# ADC_Keychain.net
KiCad netlist of a schematic drawn in EAGLE
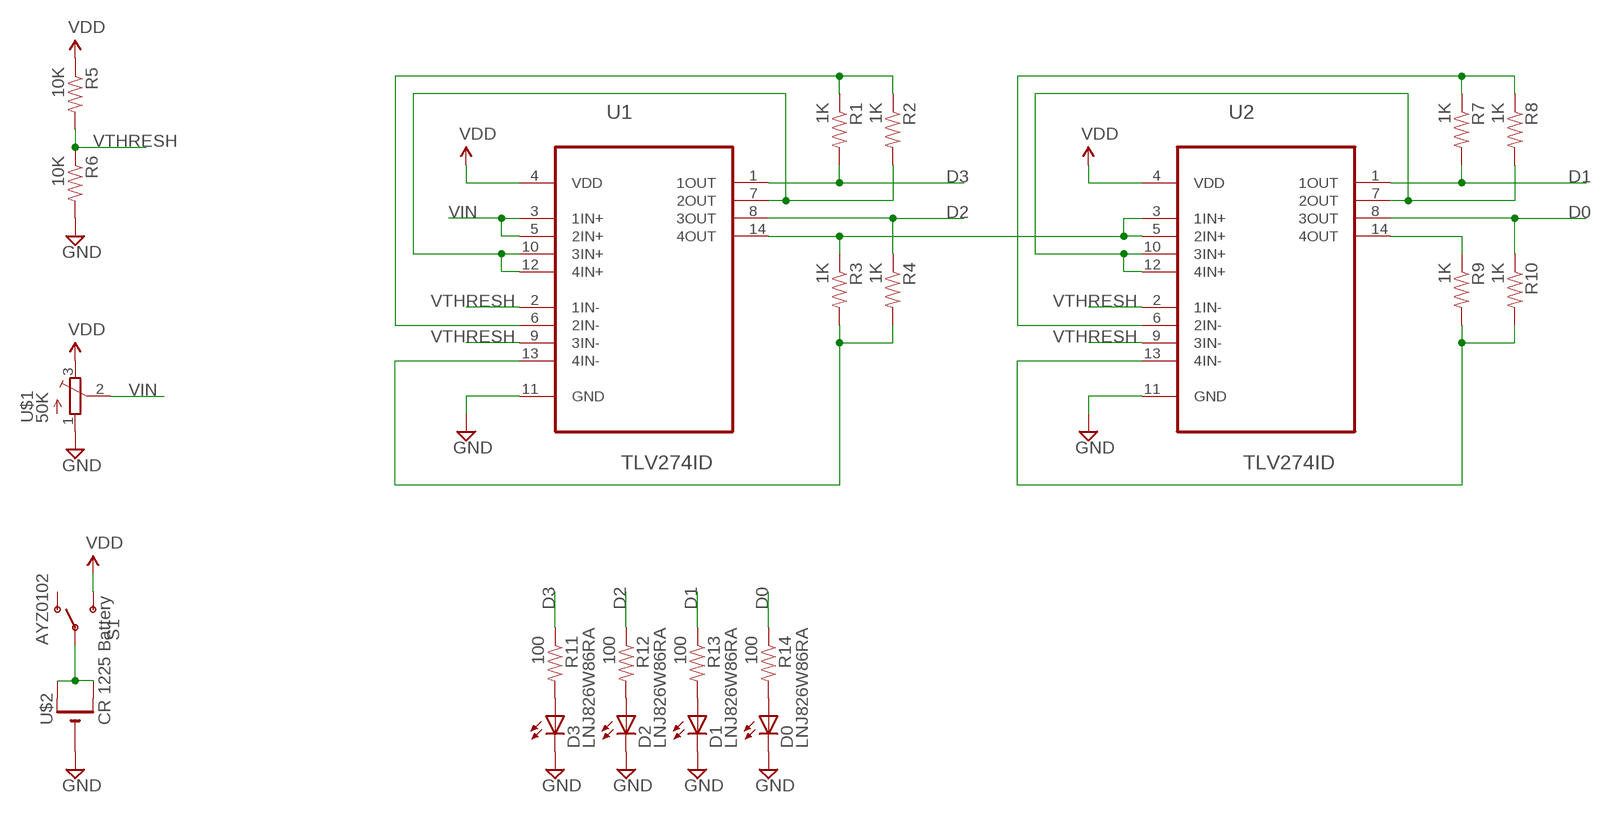
[diagram p0: schematic, sheet 1]

(export (version "E")
  (design (tool "Eeschema 10.0.6"))
  (components
    (comp (ref "D0")
      (value "LNJ826W86RA")
      (footprint "eagle-import:CHIP-LED0603")
      (libsource (lib "eagle-import") (part "LEDCHIP-LED0603"))
    )
    (comp (ref "D1")
      (value "LNJ826W86RA")
      (footprint "eagle-import:CHIP-LED0603")
      (libsource (lib "eagle-import") (part "LEDCHIP-LED0603"))
    )
    (comp (ref "D2")
      (value "LNJ826W86RA")
      (footprint "eagle-import:CHIP-LED0603")
      (libsource (lib "eagle-import") (part "LEDCHIP-LED0603"))
    )
    (comp (ref "D3")
      (value "LNJ826W86RA")
      (footprint "eagle-import:CHIP-LED0603")
      (libsource (lib "eagle-import") (part "LEDCHIP-LED0603"))
    )
    (comp (ref "R1")
      (value "1K")
      (footprint "eagle-import:0603-RES")
      (libsource (lib "eagle-import") (part "1KOHM1/10W1%(0603)"))
    )
    (comp (ref "R2")
      (value "1K")
      (footprint "eagle-import:0603-RES")
      (libsource (lib "eagle-import") (part "1KOHM1/10W1%(0603)"))
    )
    (comp (ref "R3")
      (value "1K")
      (footprint "eagle-import:0603-RES")
      (libsource (lib "eagle-import") (part "1KOHM1/10W1%(0603)"))
    )
    (comp (ref "R4")
      (value "1K")
      (footprint "eagle-import:0603-RES")
      (libsource (lib "eagle-import") (part "1KOHM1/10W1%(0603)"))
    )
    (comp (ref "R5")
      (value "10K")
      (footprint "eagle-import:0603-RES")
      (libsource (lib "eagle-import") (part "1KOHM1/10W1%(0603)"))
    )
    (comp (ref "R6")
      (value "10K")
      (footprint "eagle-import:0603-RES")
      (libsource (lib "eagle-import") (part "1KOHM1/10W1%(0603)"))
    )
    (comp (ref "R7")
      (value "1K")
      (footprint "eagle-import:0603-RES")
      (libsource (lib "eagle-import") (part "1KOHM1/10W1%(0603)"))
    )
    (comp (ref "R8")
      (value "1K")
      (footprint "eagle-import:0603-RES")
      (libsource (lib "eagle-import") (part "1KOHM1/10W1%(0603)"))
    )
    (comp (ref "R9")
      (value "1K")
      (footprint "eagle-import:0603-RES")
      (libsource (lib "eagle-import") (part "1KOHM1/10W1%(0603)"))
    )
    (comp (ref "R10")
      (value "1K")
      (footprint "eagle-import:0603-RES")
      (libsource (lib "eagle-import") (part "1KOHM1/10W1%(0603)"))
    )
    (comp (ref "R11")
      (value "100")
      (footprint "eagle-import:0603-RES")
      (libsource (lib "eagle-import") (part "1KOHM1/10W1%(0603)"))
    )
    (comp (ref "R12")
      (value "100")
      (footprint "eagle-import:0603-RES")
      (libsource (lib "eagle-import") (part "1KOHM1/10W1%(0603)"))
    )
    (comp (ref "R13")
      (value "100")
      (footprint "eagle-import:0603-RES")
      (libsource (lib "eagle-import") (part "1KOHM1/10W1%(0603)"))
    )
    (comp (ref "R14")
      (value "100")
      (footprint "eagle-import:0603-RES")
      (libsource (lib "eagle-import") (part "1KOHM1/10W1%(0603)"))
    )
    (comp (ref "S1")
      (value "AYZ0102")
      (footprint "eagle-import:SWITCH-SPDT-SMD")
      (libsource (lib "eagle-import") (part "SWITCH-SPDTSMD2"))
    )
    (comp (ref "U$1")
      (value "50K")
      (footprint "eagle-import:TC33X")
      (libsource (lib "eagle-import") (part "TRIMPOTTC33X"))
    )
    (comp (ref "U$2")
      (value "CR 1225 Battery")
      (footprint "eagle-import:CR1220-SMD")
      (libsource (lib "eagle-import") (part "CR1220SMT"))
    )
    (comp (ref "U1")
      (value "TLV274ID")
      (footprint "eagle-import:SOIC127P600X175-14N")
      (libsource (lib "eagle-import") (part "TLV274ID"))
    )
    (comp (ref "U2")
      (value "TLV274ID")
      (footprint "eagle-import:SOIC127P600X175-14N")
      (libsource (lib "eagle-import") (part "TLV274ID"))
    )
  )
  (nets
    (net (code "1") (name "/D0") (class "Default")
      (node (ref "R10") (pin "1") (pinfunction "1_1") (pintype "passive"))
      (node (ref "R14") (pin "1") (pinfunction "1_1") (pintype "passive"))
      (node (ref "U2") (pin "8") (pinfunction "3OUT_8") (pintype "output"))
    )
    (net (code "2") (name "/D1") (class "Default")
      (node (ref "R13") (pin "1") (pinfunction "1_1") (pintype "passive"))
      (node (ref "R7") (pin "2") (pinfunction "2_2") (pintype "passive"))
      (node (ref "U2") (pin "1") (pinfunction "1OUT_1") (pintype "output"))
    )
    (net (code "3") (name "/D2") (class "Default")
      (node (ref "R12") (pin "1") (pinfunction "1_1") (pintype "passive"))
      (node (ref "R4") (pin "1") (pinfunction "1_1") (pintype "passive"))
      (node (ref "U1") (pin "8") (pinfunction "3OUT_8") (pintype "output"))
    )
    (net (code "4") (name "/D3") (class "Default")
      (node (ref "R1") (pin "2") (pinfunction "2_2") (pintype "passive"))
      (node (ref "R11") (pin "1") (pinfunction "1_1") (pintype "passive"))
      (node (ref "U1") (pin "1") (pinfunction "1OUT_1") (pintype "output"))
    )
    (net (code "5") (name "/VIN") (class "Default")
      (node (ref "U$1") (pin "2") (pinfunction "S_2") (pintype "passive"))
      (node (ref "U1") (pin "3") (pinfunction "1IN+_3") (pintype "input"))
      (node (ref "U1") (pin "5") (pinfunction "2IN+_5") (pintype "input"))
    )
    (net (code "6") (name "/VTHRESH") (class "Default")
      (node (ref "R5") (pin "2") (pinfunction "2_2") (pintype "passive"))
      (node (ref "R6") (pin "1") (pinfunction "1_1") (pintype "passive"))
      (node (ref "U1") (pin "2") (pinfunction "1IN-_2") (pintype "input"))
      (node (ref "U1") (pin "9") (pinfunction "3IN-_9") (pintype "input"))
      (node (ref "U2") (pin "2") (pinfunction "1IN-_2") (pintype "input"))
      (node (ref "U2") (pin "9") (pinfunction "3IN-_9") (pintype "input"))
    )
    (net (code "7") (name "GND") (class "Default")
      (node (ref "D0") (pin "C") (pinfunction "C_C") (pintype "passive"))
      (node (ref "D1") (pin "C") (pinfunction "C_C") (pintype "passive"))
      (node (ref "D2") (pin "C") (pinfunction "C_C") (pintype "passive"))
      (node (ref "D3") (pin "C") (pinfunction "C_C") (pintype "passive"))
      (node (ref "R6") (pin "2") (pinfunction "2_2") (pintype "passive"))
      (node (ref "U$1") (pin "1") (pinfunction "A_1") (pintype "passive"))
      (node (ref "U$2") (pin "-") (pinfunction "-_-") (pintype "passive"))
      (node (ref "U1") (pin "11") (pinfunction "GND_11") (pintype "passive"))
      (node (ref "U2") (pin "11") (pinfunction "GND_11") (pintype "passive"))
    )
    (net (code "8") (name "Net-(D0-PadA)") (class "Default")
      (node (ref "D0") (pin "A") (pinfunction "A_A") (pintype "passive"))
      (node (ref "R14") (pin "2") (pinfunction "2_2") (pintype "passive"))
    )
    (net (code "9") (name "Net-(D1-PadA)") (class "Default")
      (node (ref "D1") (pin "A") (pinfunction "A_A") (pintype "passive"))
      (node (ref "R13") (pin "2") (pinfunction "2_2") (pintype "passive"))
    )
    (net (code "10") (name "Net-(D2-PadA)") (class "Default")
      (node (ref "D2") (pin "A") (pinfunction "A_A") (pintype "passive"))
      (node (ref "R12") (pin "2") (pinfunction "2_2") (pintype "passive"))
    )
    (net (code "11") (name "Net-(D3-PadA)") (class "Default")
      (node (ref "D3") (pin "A") (pinfunction "A_A") (pintype "passive"))
      (node (ref "R11") (pin "2") (pinfunction "2_2") (pintype "passive"))
    )
    (net (code "12") (name "Net-(S1-P)") (class "Default")
      (node (ref "S1") (pin "2") (pinfunction "P_2") (pintype "passive"))
      (node (ref "U$2") (pin "+$1") (pinfunction "+_+$1") (pintype "passive"))
      (node (ref "U$2") (pin "+$2") (pinfunction "+1_+$2") (pintype "passive"))
    )
    (net (code "13") (name "Net-(U1-2IN-)") (class "Default")
      (node (ref "R1") (pin "1") (pinfunction "1_1") (pintype "passive"))
      (node (ref "R2") (pin "1") (pinfunction "1_1") (pintype "passive"))
      (node (ref "U1") (pin "6") (pinfunction "2IN-_6") (pintype "input"))
    )
    (net (code "14") (name "Net-(U1-2OUT)") (class "Default")
      (node (ref "R2") (pin "2") (pinfunction "2_2") (pintype "passive"))
      (node (ref "U1") (pin "10") (pinfunction "3IN+_10") (pintype "input"))
      (node (ref "U1") (pin "12") (pinfunction "4IN+_12") (pintype "input"))
      (node (ref "U1") (pin "7") (pinfunction "2OUT_7") (pintype "output"))
    )
    (net (code "15") (name "Net-(U1-4IN-)") (class "Default")
      (node (ref "R3") (pin "2") (pinfunction "2_2") (pintype "passive"))
      (node (ref "R4") (pin "2") (pinfunction "2_2") (pintype "passive"))
      (node (ref "U1") (pin "13") (pinfunction "4IN-_13") (pintype "input"))
    )
    (net (code "16") (name "Net-(U1-4OUT)") (class "Default")
      (node (ref "R3") (pin "1") (pinfunction "1_1") (pintype "passive"))
      (node (ref "U1") (pin "14") (pinfunction "4OUT_14") (pintype "output"))
      (node (ref "U2") (pin "3") (pinfunction "1IN+_3") (pintype "input"))
      (node (ref "U2") (pin "5") (pinfunction "2IN+_5") (pintype "input"))
    )
    (net (code "17") (name "Net-(U2-2IN-)") (class "Default")
      (node (ref "R7") (pin "1") (pinfunction "1_1") (pintype "passive"))
      (node (ref "R8") (pin "1") (pinfunction "1_1") (pintype "passive"))
      (node (ref "U2") (pin "6") (pinfunction "2IN-_6") (pintype "input"))
    )
    (net (code "18") (name "Net-(U2-2OUT)") (class "Default")
      (node (ref "R8") (pin "2") (pinfunction "2_2") (pintype "passive"))
      (node (ref "U2") (pin "10") (pinfunction "3IN+_10") (pintype "input"))
      (node (ref "U2") (pin "12") (pinfunction "4IN+_12") (pintype "input"))
      (node (ref "U2") (pin "7") (pinfunction "2OUT_7") (pintype "output"))
    )
    (net (code "19") (name "Net-(U2-4IN-)") (class "Default")
      (node (ref "R10") (pin "2") (pinfunction "2_2") (pintype "passive"))
      (node (ref "R9") (pin "2") (pinfunction "2_2") (pintype "passive"))
      (node (ref "U2") (pin "13") (pinfunction "4IN-_13") (pintype "input"))
    )
    (net (code "20") (name "Net-(U2-4OUT)") (class "Default")
      (node (ref "R9") (pin "1") (pinfunction "1_1") (pintype "passive"))
      (node (ref "U2") (pin "14") (pinfunction "4OUT_14") (pintype "output"))
    )
    (net (code "21") (name "VDD") (class "Default")
      (node (ref "R5") (pin "1") (pinfunction "1_1") (pintype "passive"))
      (node (ref "S1") (pin "3") (pinfunction "S_3") (pintype "passive"))
      (node (ref "U$1") (pin "3") (pinfunction "E_3") (pintype "passive"))
      (node (ref "U1") (pin "4") (pinfunction "VDD_4") (pintype "power_in"))
      (node (ref "U2") (pin "4") (pinfunction "VDD_4") (pintype "power_in"))
    )
    (net (code "22") (name "unconnected-(S1-O-Pad1)") (class "Default")
      (node (ref "S1") (pin "1") (pinfunction "O_1") (pintype "passive"))
    )
  )
)
